# Advanced_Breakout_Shield.net
KiCad netlist of a schematic drawn in EAGLE
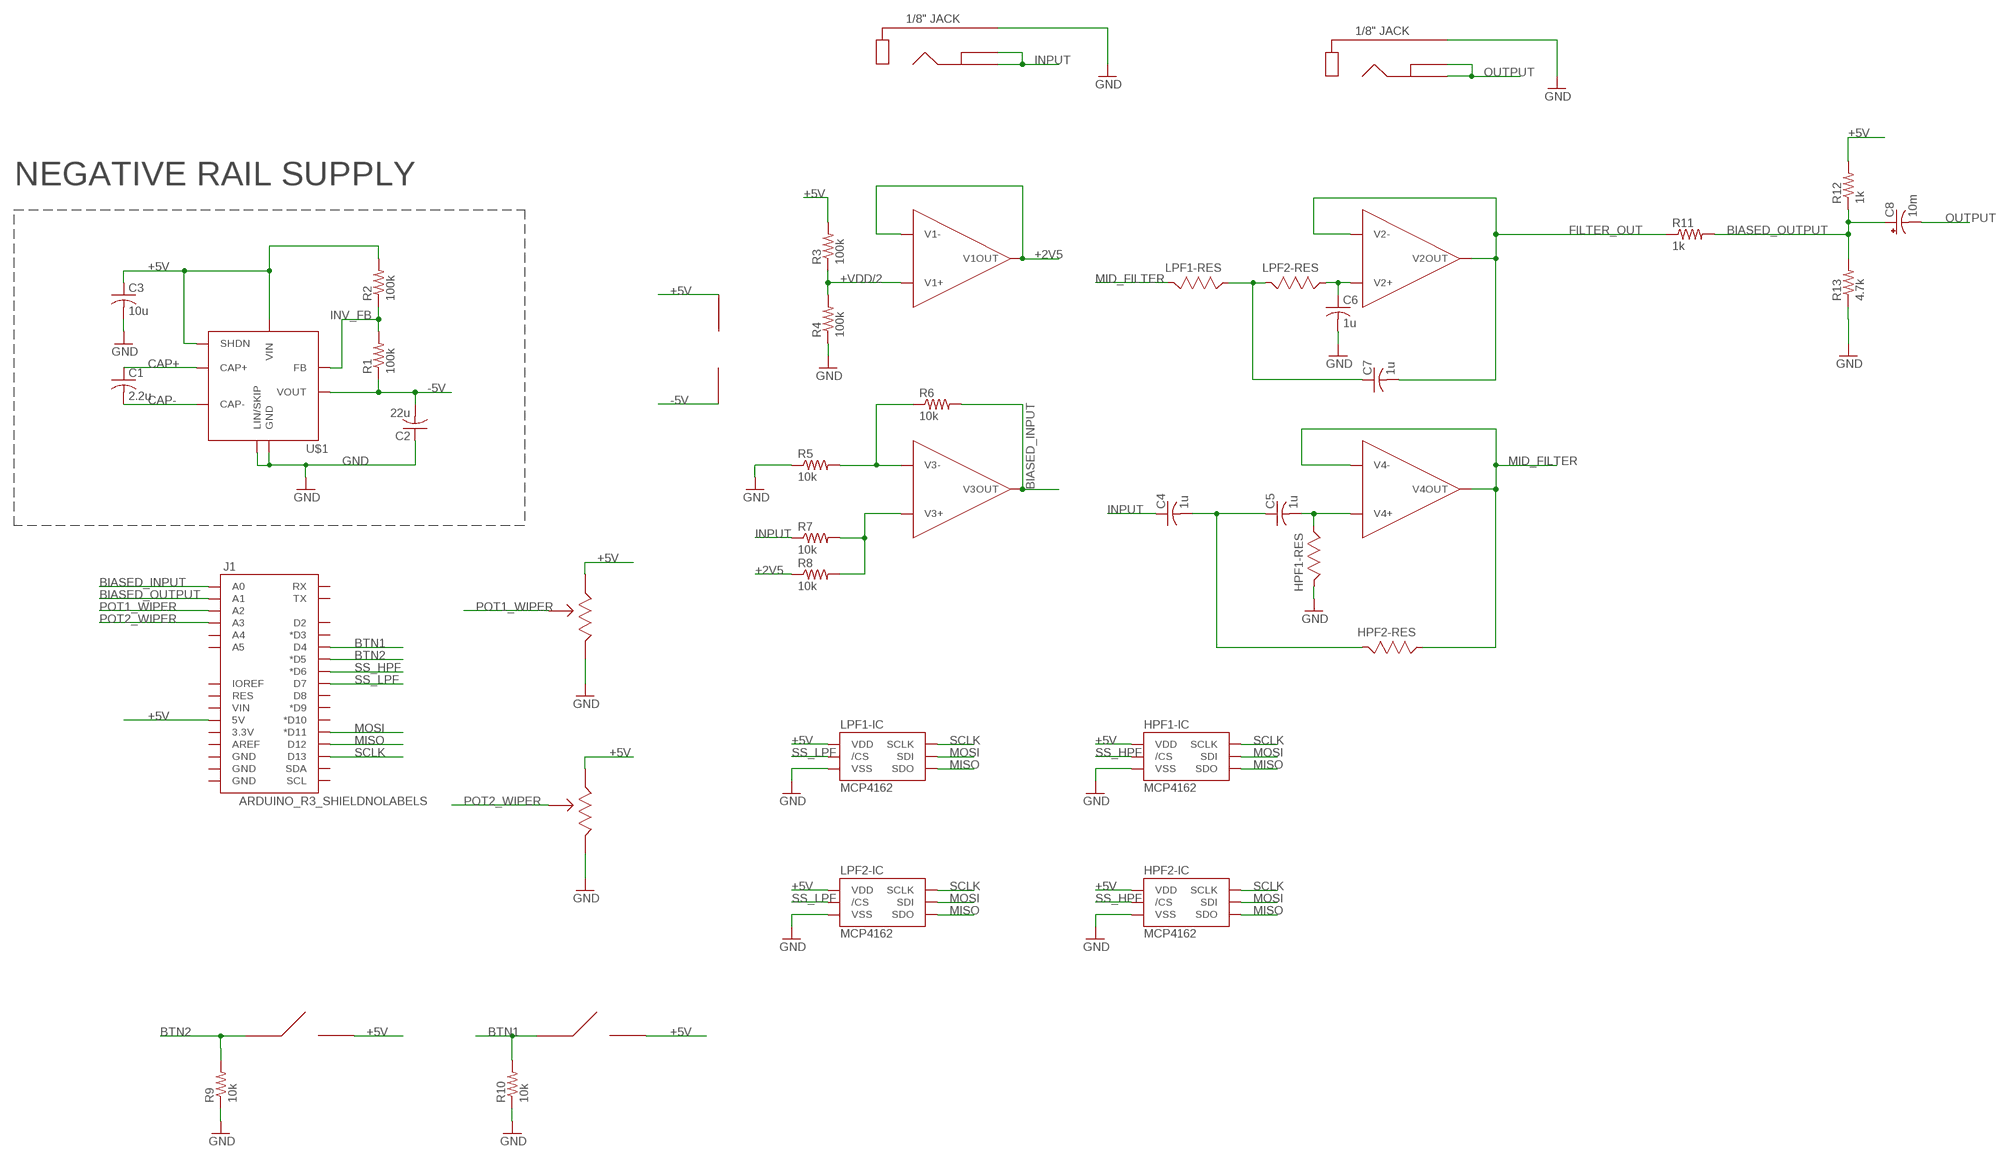
[diagram p0: schematic, sheet 1]

(export (version "E")
  (design (tool "Eeschema 10.0.6"))
  (components
    (comp (ref "C1")
      (value "2.2u")
      (footprint "eagle-import:C1206K")
      (libsource (lib "eagle-import") (part "C-USC1206K"))
    )
    (comp (ref "C2")
      (value "22u")
      (footprint "eagle-import:C1206K")
      (libsource (lib "eagle-import") (part "C-USC1206K"))
    )
    (comp (ref "C3")
      (value "10u")
      (footprint "eagle-import:C1206K")
      (libsource (lib "eagle-import") (part "C-USC1206K"))
    )
    (comp (ref "C4")
      (value "1u")
      (footprint "eagle-import:C1206K")
      (libsource (lib "eagle-import") (part "C-USC1206K"))
    )
    (comp (ref "C5")
      (value "1u")
      (footprint "eagle-import:C1206K")
      (libsource (lib "eagle-import") (part "C-USC1206K"))
    )
    (comp (ref "C6")
      (value "1u")
      (footprint "eagle-import:C1206K")
      (libsource (lib "eagle-import") (part "C-USC1206K"))
    )
    (comp (ref "C7")
      (value "1u")
      (footprint "eagle-import:C1206K")
      (libsource (lib "eagle-import") (part "C-USC1206K"))
    )
    (comp (ref "C8")
      (value "10m")
      (footprint "eagle-import:E7,5-16")
      (libsource (lib "eagle-import") (part "CPOL-USE7.5-16"))
    )
    (comp (ref "HPF1")
      (value "MCP4162-502E")
      (footprint "eagle-import:DIL08")
      (libsource (lib "eagle-import") (part "MCP4162-502E"))
    )
    (comp (ref "HPF2")
      (value "MCP4162-502E")
      (footprint "eagle-import:DIL08")
      (libsource (lib "eagle-import") (part "MCP4162-502E"))
    )
    (comp (ref "J1")
      (value "ARDUINO_R3_SHIELDNOLABELS")
      (footprint "eagle-import:UNO_R3_SHIELD_NOLABELS")
      (libsource (lib "eagle-import") (part "ARDUINO_R3_SHIELDNOLABELS"))
    )
    (comp (ref "LPF1")
      (value "MCP4162-502E")
      (footprint "eagle-import:DIL08")
      (libsource (lib "eagle-import") (part "MCP4162-502E"))
    )
    (comp (ref "LPF2")
      (value "MCP4162-502E")
      (footprint "eagle-import:DIL08")
      (libsource (lib "eagle-import") (part "MCP4162-502E"))
    )
    (comp (ref "R1")
      (value "100k")
      (footprint "eagle-import:R1210")
      (libsource (lib "eagle-import") (part "R-US_R1210"))
    )
    (comp (ref "R2")
      (value "100k")
      (footprint "eagle-import:R1210")
      (libsource (lib "eagle-import") (part "R-US_R1210"))
    )
    (comp (ref "R3")
      (value "100k")
      (footprint "eagle-import:R1210")
      (libsource (lib "eagle-import") (part "R-US_R1210"))
    )
    (comp (ref "R4")
      (value "100k")
      (footprint "eagle-import:R1210")
      (libsource (lib "eagle-import") (part "R-US_R1210"))
    )
    (comp (ref "R5")
      (value "10k")
      (footprint "eagle-import:R1210")
      (libsource (lib "eagle-import") (part "R-US_R1210"))
    )
    (comp (ref "R6")
      (value "10k")
      (footprint "eagle-import:R1210")
      (libsource (lib "eagle-import") (part "R-US_R1210"))
    )
    (comp (ref "R7")
      (value "10k")
      (footprint "eagle-import:R1210")
      (libsource (lib "eagle-import") (part "R-US_R1210"))
    )
    (comp (ref "R8")
      (value "10k")
      (footprint "eagle-import:R1210")
      (libsource (lib "eagle-import") (part "R-US_R1210"))
    )
    (comp (ref "R9")
      (value "10k")
      (footprint "eagle-import:R1210")
      (libsource (lib "eagle-import") (part "R-US_R1210"))
    )
    (comp (ref "R10")
      (value "10k")
      (footprint "eagle-import:R1210")
      (libsource (lib "eagle-import") (part "R-US_R1210"))
    )
    (comp (ref "R11")
      (value "1k")
      (footprint "eagle-import:R1210")
      (libsource (lib "eagle-import") (part "R-US_R1210"))
    )
    (comp (ref "R12")
      (value "1k")
      (footprint "eagle-import:R1210")
      (libsource (lib "eagle-import") (part "R-US_R1210"))
    )
    (comp (ref "R13")
      (value "4.7k")
      (footprint "eagle-import:R1210")
      (libsource (lib "eagle-import") (part "R-US_R1210"))
    )
    (comp (ref "U$1")
      (value "MAX1673")
      (footprint "eagle-import:SO08")
      (libsource (lib "eagle-import") (part "MAX1673ESA"))
    )
    (comp (ref "U$2")
      (value "TLV974")
      (footprint "eagle-import:DIL14")
      (libsource (lib "eagle-import") (part "TLV974"))
    )
    (comp (ref "U$3")
      (value "P120PK")
      (footprint "eagle-import:P120PK")
      (libsource (lib "eagle-import") (part "P120PK"))
    )
    (comp (ref "U$4")
      (value "P120PK")
      (footprint "eagle-import:P120PK")
      (libsource (lib "eagle-import") (part "P120PK"))
    )
    (comp (ref "U$5")
      (value "AUDIO_JACK")
      (footprint "eagle-import:AUDIO_JACK")
      (libsource (lib "eagle-import") (part "AUDIO_JACK"))
    )
    (comp (ref "U$6")
      (value "AUDIO_JACK")
      (footprint "eagle-import:AUDIO_JACK")
      (libsource (lib "eagle-import") (part "AUDIO_JACK"))
    )
    (comp (ref "U$7")
      (value "IEEE_LOGO_BUTTON")
      (footprint "eagle-import:IEEE_LOGO_BUTTON")
      (libsource (lib "eagle-import") (part "IEEE_LOGO_BUTTON"))
    )
    (comp (ref "U$8")
      (value "IEEE_LOGO_BUTTON")
      (footprint "eagle-import:IEEE_LOGO_BUTTON")
      (libsource (lib "eagle-import") (part "IEEE_LOGO_BUTTON"))
    )
  )
  (nets
    (net (code "1") (name "/+2V5") (class "Default")
      (node (ref "R8") (pin "1") (pinfunction "1_1") (pintype "passive"))
      (node (ref "U$2") (pin "1") (pinfunction "V1OUT_1") (pintype "bidirectional"))
      (node (ref "U$2") (pin "2") (pinfunction "V1-_2") (pintype "bidirectional"))
    )
    (net (code "2") (name "/+5V") (class "Default")
      (node (ref "C3") (pin "1") (pinfunction "1_1") (pintype "passive"))
      (node (ref "HPF1") (pin "8") (pinfunction "VDD_8") (pintype "bidirectional"))
      (node (ref "HPF2") (pin "8") (pinfunction "VDD_8") (pintype "bidirectional"))
      (node (ref "J1") (pin "5V") (pinfunction "5V_5V") (pintype "bidirectional"))
      (node (ref "LPF1") (pin "8") (pinfunction "VDD_8") (pintype "bidirectional"))
      (node (ref "LPF2") (pin "8") (pinfunction "VDD_8") (pintype "bidirectional"))
      (node (ref "R12") (pin "2") (pinfunction "2_2") (pintype "passive"))
      (node (ref "R2") (pin "2") (pinfunction "2_2") (pintype "passive"))
      (node (ref "R3") (pin "2") (pinfunction "2_2") (pintype "passive"))
      (node (ref "U$1") (pin "4") (pinfunction "SHDN_4") (pintype "bidirectional"))
      (node (ref "U$1") (pin "8") (pinfunction "VIN_8") (pintype "bidirectional"))
      (node (ref "U$2") (pin "4") (pinfunction "+VCC_4") (pintype "bidirectional"))
      (node (ref "U$3") (pin "PR") (pinfunction "RA_PR") (pintype "bidirectional"))
      (node (ref "U$4") (pin "PR") (pinfunction "RA_PR") (pintype "bidirectional"))
      (node (ref "U$7") (pin "P$2") (pinfunction "P$2_P$2") (pintype "bidirectional"))
      (node (ref "U$8") (pin "P$2") (pinfunction "P$2_P$2") (pintype "bidirectional"))
    )
    (net (code "3") (name "/+VDD{slash}2") (class "Default")
      (node (ref "R3") (pin "1") (pinfunction "1_1") (pintype "passive"))
      (node (ref "R4") (pin "2") (pinfunction "2_2") (pintype "passive"))
      (node (ref "U$2") (pin "3") (pinfunction "V1+_3") (pintype "bidirectional"))
    )
    (net (code "4") (name "/-5V") (class "Default")
      (node (ref "C2") (pin "2") (pinfunction "2_2") (pintype "passive"))
      (node (ref "R1") (pin "1") (pinfunction "1_1") (pintype "passive"))
      (node (ref "U$1") (pin "5") (pinfunction "VOUT_5") (pintype "bidirectional"))
      (node (ref "U$2") (pin "11") (pinfunction "-VCC_11") (pintype "bidirectional"))
    )
    (net (code "5") (name "/BIASED_INPUT") (class "Default")
      (node (ref "J1") (pin "A0") (pinfunction "A0_A0") (pintype "bidirectional"))
      (node (ref "R6") (pin "2") (pinfunction "2_2") (pintype "passive"))
      (node (ref "U$2") (pin "8") (pinfunction "V3OUT_8") (pintype "bidirectional"))
    )
    (net (code "6") (name "/BIASED_OUTPUT") (class "Default")
      (node (ref "C8") (pin "+") (pinfunction "+_+") (pintype "passive"))
      (node (ref "J1") (pin "A1") (pinfunction "A1_A1") (pintype "bidirectional"))
      (node (ref "R11") (pin "2") (pinfunction "2_2") (pintype "passive"))
      (node (ref "R12") (pin "1") (pinfunction "1_1") (pintype "passive"))
      (node (ref "R13") (pin "2") (pinfunction "2_2") (pintype "passive"))
    )
    (net (code "7") (name "/BTN1") (class "Default")
      (node (ref "J1") (pin "D4") (pinfunction "D4_D4") (pintype "bidirectional"))
      (node (ref "R10") (pin "2") (pinfunction "2_2") (pintype "passive"))
      (node (ref "U$8") (pin "P$1") (pinfunction "P$1_P$1") (pintype "bidirectional"))
    )
    (net (code "8") (name "/BTN2") (class "Default")
      (node (ref "J1") (pin "D5") (pinfunction "*D5_D5") (pintype "bidirectional"))
      (node (ref "R9") (pin "2") (pinfunction "2_2") (pintype "passive"))
      (node (ref "U$7") (pin "P$1") (pinfunction "P$1_P$1") (pintype "bidirectional"))
    )
    (net (code "9") (name "/CAP+") (class "Default")
      (node (ref "C1") (pin "1") (pinfunction "1_1") (pintype "passive"))
      (node (ref "U$1") (pin "2") (pinfunction "CAP+_2") (pintype "bidirectional"))
    )
    (net (code "10") (name "/CAP-") (class "Default")
      (node (ref "C1") (pin "2") (pinfunction "2_2") (pintype "passive"))
      (node (ref "U$1") (pin "3") (pinfunction "CAP-_3") (pintype "bidirectional"))
    )
    (net (code "11") (name "/FILTER_OUT") (class "Default")
      (node (ref "C7") (pin "2") (pinfunction "2_2") (pintype "passive"))
      (node (ref "R11") (pin "1") (pinfunction "1_1") (pintype "passive"))
      (node (ref "U$2") (pin "6") (pinfunction "V2-_6") (pintype "bidirectional"))
      (node (ref "U$2") (pin "7") (pinfunction "V2OUT_7") (pintype "bidirectional"))
    )
    (net (code "12") (name "/INPUT") (class "Default")
      (node (ref "C4") (pin "1") (pinfunction "1_1") (pintype "passive"))
      (node (ref "R7") (pin "1") (pinfunction "1_1") (pintype "passive"))
      (node (ref "U$5") (pin "RING") (pinfunction "RING_RING") (pintype "bidirectional"))
      (node (ref "U$5") (pin "TIP") (pinfunction "TIP_TIP") (pintype "bidirectional"))
    )
    (net (code "13") (name "/INV_FB") (class "Default")
      (node (ref "R1") (pin "2") (pinfunction "2_2") (pintype "passive"))
      (node (ref "R2") (pin "1") (pinfunction "1_1") (pintype "passive"))
      (node (ref "U$1") (pin "6") (pinfunction "FB_6") (pintype "bidirectional"))
    )
    (net (code "14") (name "/MID_FILTER") (class "Default")
      (node (ref "HPF2") (pin "5") (pinfunction "WIPER_5") (pintype "bidirectional"))
      (node (ref "LPF1") (pin "6") (pinfunction "BASE_6") (pintype "bidirectional"))
      (node (ref "U$2") (pin "13") (pinfunction "V4-_13") (pintype "bidirectional"))
      (node (ref "U$2") (pin "14") (pinfunction "V4OUT_14") (pintype "bidirectional"))
    )
    (net (code "15") (name "/MISO") (class "Default")
      (node (ref "HPF1") (pin "7") (pinfunction "SDO_7") (pintype "bidirectional"))
      (node (ref "HPF2") (pin "7") (pinfunction "SDO_7") (pintype "bidirectional"))
      (node (ref "J1") (pin "D12") (pinfunction "D12_D12") (pintype "bidirectional"))
      (node (ref "LPF1") (pin "7") (pinfunction "SDO_7") (pintype "bidirectional"))
      (node (ref "LPF2") (pin "7") (pinfunction "SDO_7") (pintype "bidirectional"))
    )
    (net (code "16") (name "/MOSI") (class "Default")
      (node (ref "HPF1") (pin "3") (pinfunction "SDI_3") (pintype "bidirectional"))
      (node (ref "HPF2") (pin "3") (pinfunction "SDI_3") (pintype "bidirectional"))
      (node (ref "J1") (pin "D11") (pinfunction "*D11_D11") (pintype "bidirectional"))
      (node (ref "LPF1") (pin "3") (pinfunction "SDI_3") (pintype "bidirectional"))
      (node (ref "LPF2") (pin "3") (pinfunction "SDI_3") (pintype "bidirectional"))
    )
    (net (code "17") (name "/OUTPUT") (class "Default")
      (node (ref "C8") (pin "-") (pinfunction "-_-") (pintype "passive"))
      (node (ref "U$6") (pin "RING") (pinfunction "RING_RING") (pintype "bidirectional"))
      (node (ref "U$6") (pin "TIP") (pinfunction "TIP_TIP") (pintype "bidirectional"))
    )
    (net (code "18") (name "/POT1_WIPER") (class "Default")
      (node (ref "J1") (pin "A2") (pinfunction "A2_A2") (pintype "bidirectional"))
      (node (ref "U$3") (pin "PL") (pinfunction "RW_PL") (pintype "bidirectional"))
    )
    (net (code "19") (name "/POT2_WIPER") (class "Default")
      (node (ref "J1") (pin "A3") (pinfunction "A3_A3") (pintype "bidirectional"))
      (node (ref "U$4") (pin "PL") (pinfunction "RW_PL") (pintype "bidirectional"))
    )
    (net (code "20") (name "/SCLK") (class "Default")
      (node (ref "HPF1") (pin "2") (pinfunction "SCLK_2") (pintype "bidirectional"))
      (node (ref "HPF2") (pin "2") (pinfunction "SCLK_2") (pintype "bidirectional"))
      (node (ref "J1") (pin "D13") (pinfunction "D13_D13") (pintype "bidirectional"))
      (node (ref "LPF1") (pin "2") (pinfunction "SCLK_2") (pintype "bidirectional"))
      (node (ref "LPF2") (pin "2") (pinfunction "SCLK_2") (pintype "bidirectional"))
    )
    (net (code "21") (name "/SS_HPF") (class "Default")
      (node (ref "HPF1") (pin "1") (pinfunction "/CS_1") (pintype "bidirectional"))
      (node (ref "HPF2") (pin "1") (pinfunction "/CS_1") (pintype "bidirectional"))
      (node (ref "J1") (pin "D6") (pinfunction "*D6_D6") (pintype "bidirectional"))
    )
    (net (code "22") (name "/SS_LPF") (class "Default")
      (node (ref "J1") (pin "D7") (pinfunction "D7_D7") (pintype "bidirectional"))
      (node (ref "LPF1") (pin "1") (pinfunction "/CS_1") (pintype "bidirectional"))
      (node (ref "LPF2") (pin "1") (pinfunction "/CS_1") (pintype "bidirectional"))
    )
    (net (code "23") (name "GND") (class "Default")
      (node (ref "C2") (pin "1") (pinfunction "1_1") (pintype "passive"))
      (node (ref "C3") (pin "2") (pinfunction "2_2") (pintype "passive"))
      (node (ref "C6") (pin "2") (pinfunction "2_2") (pintype "passive"))
      (node (ref "HPF1") (pin "4") (pinfunction "VSS_4") (pintype "bidirectional"))
      (node (ref "HPF1") (pin "6") (pinfunction "BASE_6") (pintype "bidirectional"))
      (node (ref "HPF2") (pin "4") (pinfunction "VSS_4") (pintype "bidirectional"))
      (node (ref "LPF1") (pin "4") (pinfunction "VSS_4") (pintype "bidirectional"))
      (node (ref "LPF2") (pin "4") (pinfunction "VSS_4") (pintype "bidirectional"))
      (node (ref "R10") (pin "1") (pinfunction "1_1") (pintype "passive"))
      (node (ref "R13") (pin "1") (pinfunction "1_1") (pintype "passive"))
      (node (ref "R4") (pin "1") (pinfunction "1_1") (pintype "passive"))
      (node (ref "R5") (pin "1") (pinfunction "1_1") (pintype "passive"))
      (node (ref "R9") (pin "1") (pinfunction "1_1") (pintype "passive"))
      (node (ref "U$1") (pin "1") (pinfunction "LIN/SKIP_1") (pintype "bidirectional"))
      (node (ref "U$1") (pin "7") (pinfunction "GND_7") (pintype "bidirectional"))
      (node (ref "U$3") (pin "PM") (pinfunction "RB_PM") (pintype "bidirectional"))
      (node (ref "U$4") (pin "PM") (pinfunction "RB_PM") (pintype "bidirectional"))
      (node (ref "U$5") (pin "SLEEVE") (pinfunction "SLEEVE_SLEEVE") (pintype "bidirectional"))
      (node (ref "U$6") (pin "SLEEVE") (pinfunction "SLEEVE_SLEEVE") (pintype "bidirectional"))
    )
    (net (code "24") (name "Net-(HPF1B-WIPER)") (class "Default")
      (node (ref "C5") (pin "2") (pinfunction "2_2") (pintype "passive"))
      (node (ref "HPF1") (pin "5") (pinfunction "WIPER_5") (pintype "bidirectional"))
      (node (ref "U$2") (pin "12") (pinfunction "V4+_12") (pintype "bidirectional"))
    )
    (net (code "25") (name "Net-(HPF2B-BASE)") (class "Default")
      (node (ref "C4") (pin "2") (pinfunction "2_2") (pintype "passive"))
      (node (ref "C5") (pin "1") (pinfunction "1_1") (pintype "passive"))
      (node (ref "HPF2") (pin "6") (pinfunction "BASE_6") (pintype "bidirectional"))
    )
    (net (code "26") (name "Net-(LPF1B-WIPER)") (class "Default")
      (node (ref "C7") (pin "1") (pinfunction "1_1") (pintype "passive"))
      (node (ref "LPF1") (pin "5") (pinfunction "WIPER_5") (pintype "bidirectional"))
      (node (ref "LPF2") (pin "6") (pinfunction "BASE_6") (pintype "bidirectional"))
    )
    (net (code "27") (name "Net-(LPF2B-WIPER)") (class "Default")
      (node (ref "C6") (pin "1") (pinfunction "1_1") (pintype "passive"))
      (node (ref "LPF2") (pin "5") (pinfunction "WIPER_5") (pintype "bidirectional"))
      (node (ref "U$2") (pin "5") (pinfunction "V2+_5") (pintype "bidirectional"))
    )
    (net (code "28") (name "Net-(U$2-V3+)") (class "Default")
      (node (ref "R7") (pin "2") (pinfunction "2_2") (pintype "passive"))
      (node (ref "R8") (pin "2") (pinfunction "2_2") (pintype "passive"))
      (node (ref "U$2") (pin "10") (pinfunction "V3+_10") (pintype "bidirectional"))
    )
    (net (code "29") (name "Net-(U$2-V3-)") (class "Default")
      (node (ref "R5") (pin "2") (pinfunction "2_2") (pintype "passive"))
      (node (ref "R6") (pin "1") (pinfunction "1_1") (pintype "passive"))
      (node (ref "U$2") (pin "9") (pinfunction "V3-_9") (pintype "bidirectional"))
    )
    (net (code "30") (name "unconnected-(J1-*D3-PadD3)") (class "Default")
      (node (ref "J1") (pin "D3") (pinfunction "*D3_D3") (pintype "bidirectional"))
    )
    (net (code "31") (name "unconnected-(J1-*D9-PadD9)") (class "Default")
      (node (ref "J1") (pin "D9") (pinfunction "*D9_D9") (pintype "bidirectional"))
    )
    (net (code "32") (name "unconnected-(J1-*D10-PadD10)") (class "Default")
      (node (ref "J1") (pin "D10") (pinfunction "*D10_D10") (pintype "bidirectional"))
    )
    (net (code "33") (name "unconnected-(J1-GND-PadGND@0)") (class "Default")
      (node (ref "J1") (pin "GND@0") (pinfunction "GND_GND@0") (pintype "bidirectional"))
    )
    (net (code "34") (name "unconnected-(J1-GND-PadGND@1)") (class "Default")
      (node (ref "J1") (pin "GND@1") (pinfunction "GND_GND@1") (pintype "bidirectional"))
    )
    (net (code "35") (name "unconnected-(J1-GND-PadGND@2)") (class "Default")
      (node (ref "J1") (pin "GND@2") (pinfunction "GND_GND@2") (pintype "bidirectional"))
    )
    (net (code "36") (name "unconnected-(J1-Pad3.3V)") (class "Default")
      (node (ref "J1") (pin "3.3V") (pinfunction "3.3V_3.3V") (pintype "bidirectional"))
    )
    (net (code "37") (name "unconnected-(J1-PadA4)") (class "Default")
      (node (ref "J1") (pin "A4") (pinfunction "A4_A4") (pintype "bidirectional"))
    )
    (net (code "38") (name "unconnected-(J1-PadA5)") (class "Default")
      (node (ref "J1") (pin "A5") (pinfunction "A5_A5") (pintype "bidirectional"))
    )
    (net (code "39") (name "unconnected-(J1-PadAREF)") (class "Default")
      (node (ref "J1") (pin "AREF") (pinfunction "AREF_AREF") (pintype "bidirectional"))
    )
    (net (code "40") (name "unconnected-(J1-PadD2)") (class "Default")
      (node (ref "J1") (pin "D2") (pinfunction "D2_D2") (pintype "bidirectional"))
    )
    (net (code "41") (name "unconnected-(J1-PadD8)") (class "Default")
      (node (ref "J1") (pin "D8") (pinfunction "D8_D8") (pintype "bidirectional"))
    )
    (net (code "42") (name "unconnected-(J1-PadIOREF)") (class "Default")
      (node (ref "J1") (pin "IOREF") (pinfunction "IOREF_IOREF") (pintype "bidirectional"))
    )
    (net (code "43") (name "unconnected-(J1-PadRES)") (class "Default")
      (node (ref "J1") (pin "RES") (pinfunction "RES_RES") (pintype "bidirectional"))
    )
    (net (code "44") (name "unconnected-(J1-PadRX)") (class "Default")
      (node (ref "J1") (pin "RX") (pinfunction "RX_RX") (pintype "bidirectional"))
    )
    (net (code "45") (name "unconnected-(J1-PadSCL)") (class "Default")
      (node (ref "J1") (pin "SCL") (pinfunction "SCL_SCL") (pintype "bidirectional"))
    )
    (net (code "46") (name "unconnected-(J1-PadSDA)") (class "Default")
      (node (ref "J1") (pin "SDA") (pinfunction "SDA_SDA") (pintype "bidirectional"))
    )
    (net (code "47") (name "unconnected-(J1-PadTX)") (class "Default")
      (node (ref "J1") (pin "TX") (pinfunction "TX_TX") (pintype "bidirectional"))
    )
    (net (code "48") (name "unconnected-(J1-PadVIN)") (class "Default")
      (node (ref "J1") (pin "VIN") (pinfunction "VIN_VIN") (pintype "bidirectional"))
    )
  )
)
